# 468332_001_Power.net
KiCad netlist of a schematic drawn in Altium Designer
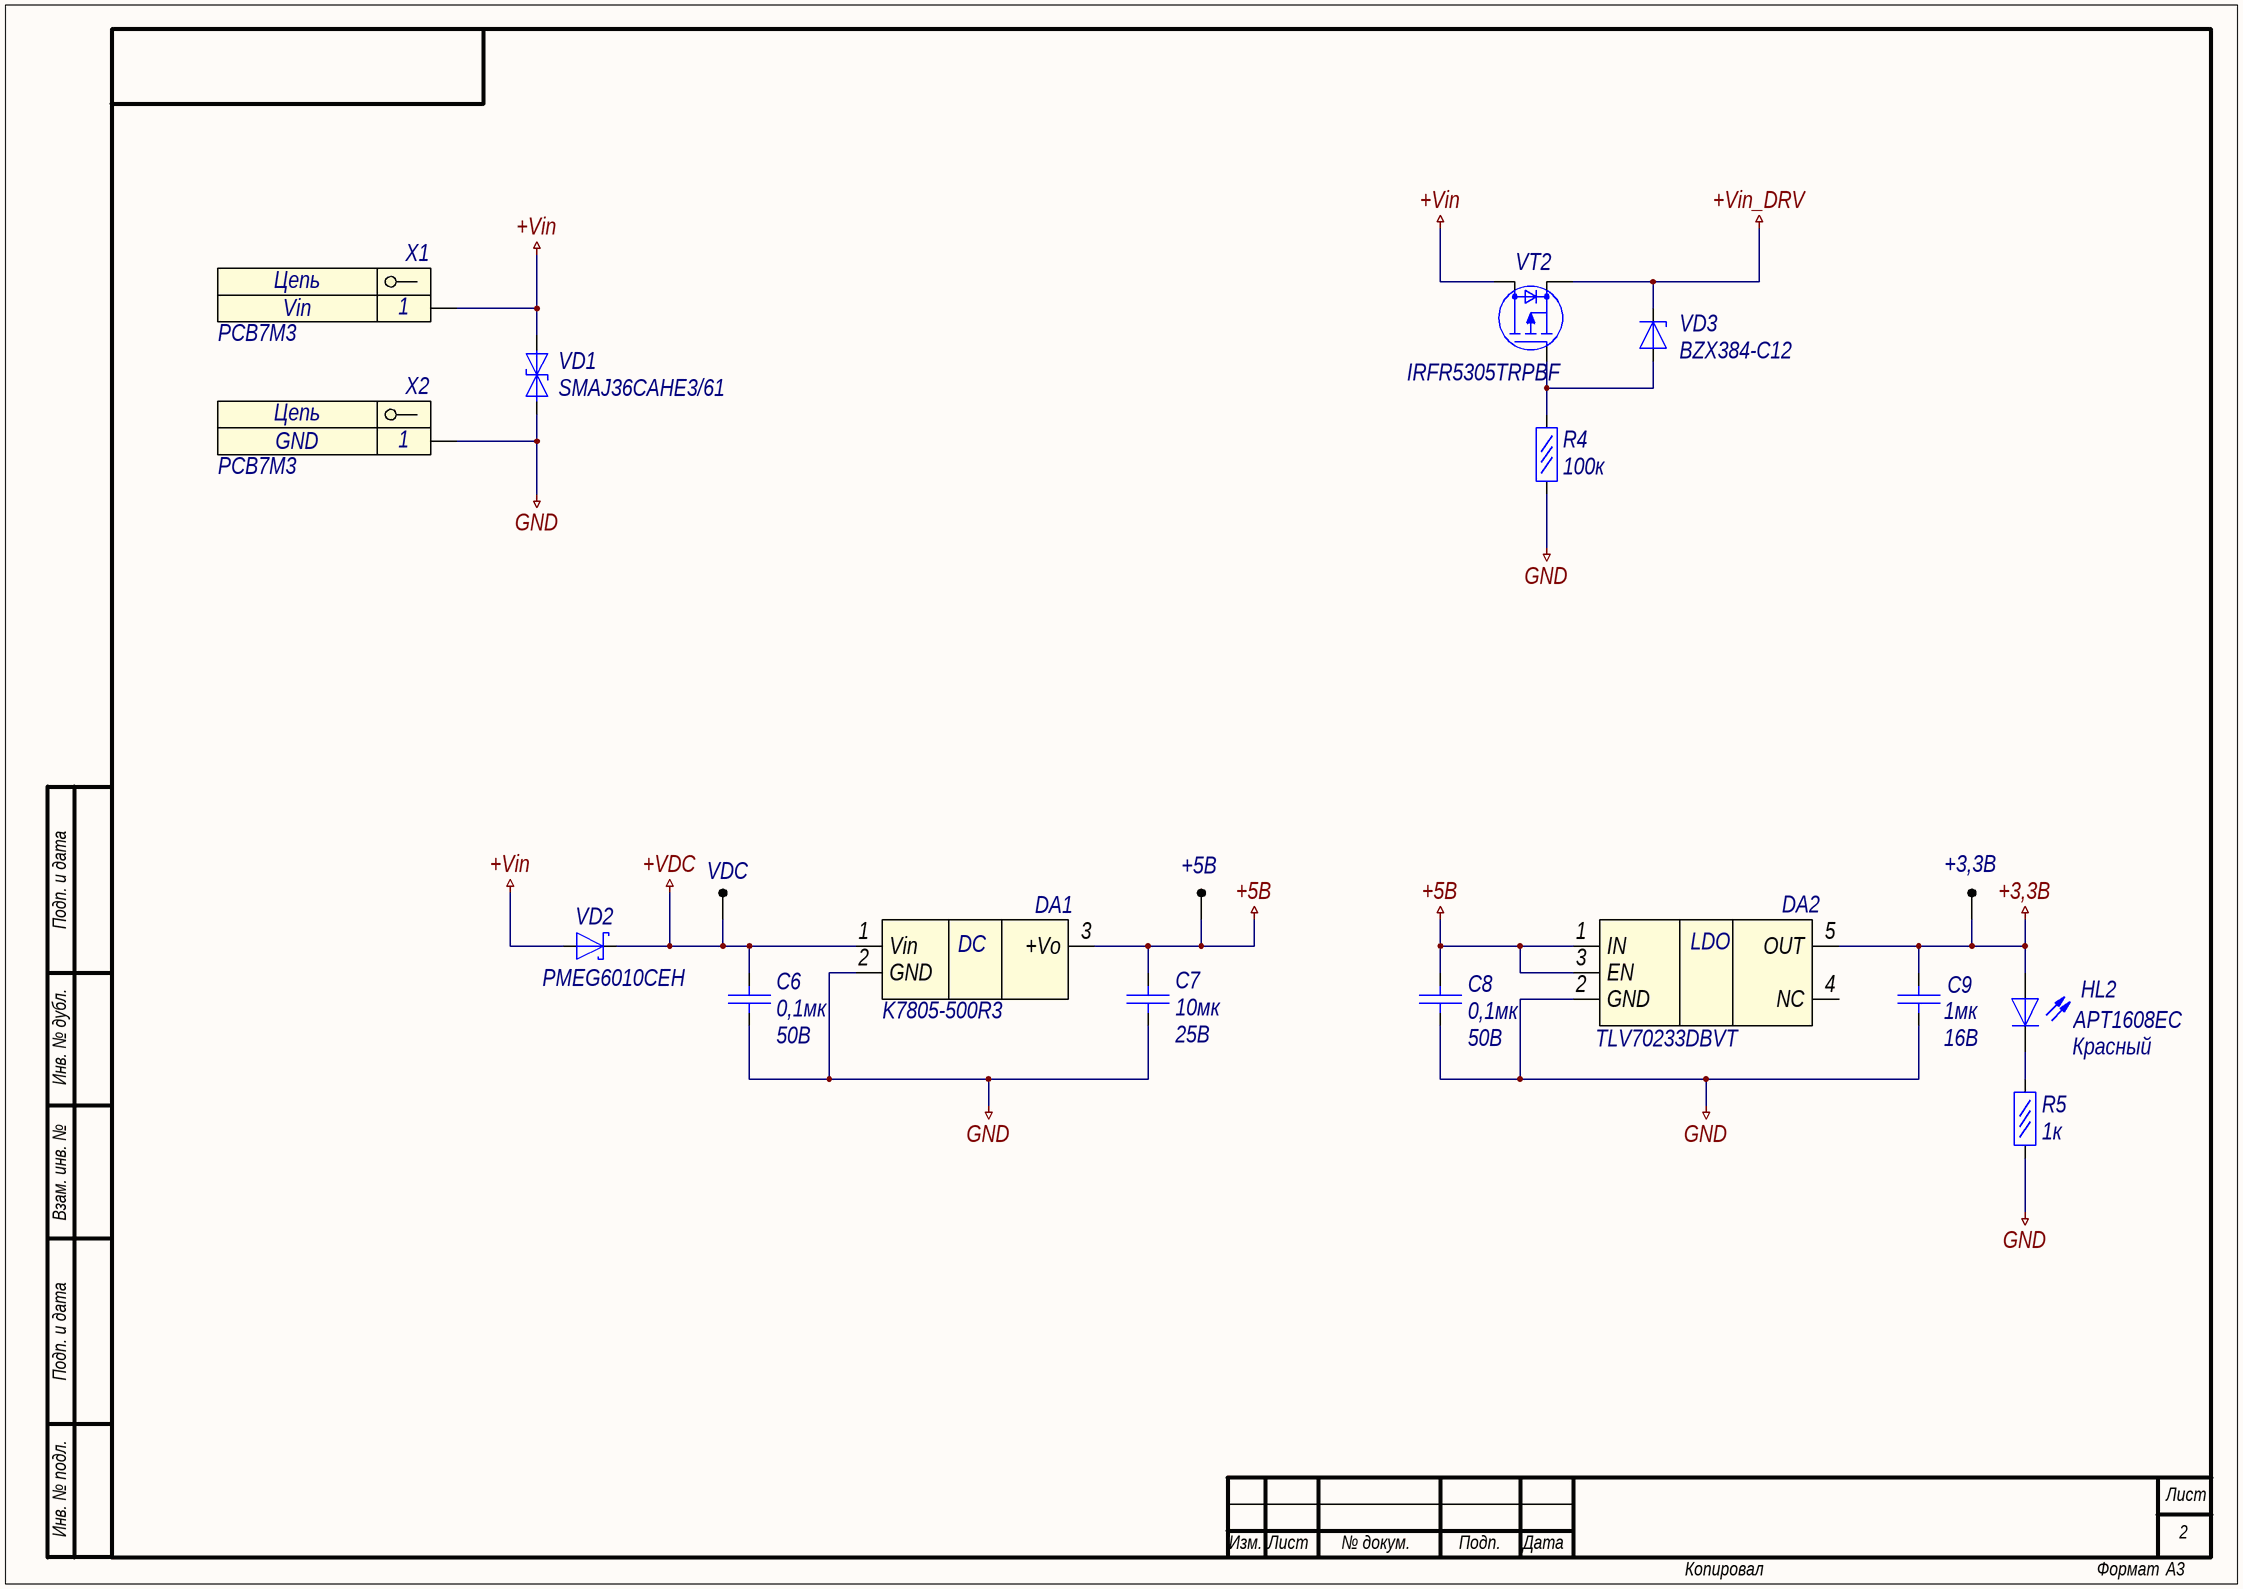
[diagram p0: РЕУН.468332.001_Power.SchDoc]

(export (version "E")
  (design (tool "Eeschema 10.0.6"))
  (components
    (comp (ref "+3,3В")
      (value "\"1\"")
      (footprint "0.5 x 1_round")
      (description "Test point")
      (libsource (lib "TarabusLib_KOR") (part "TestPoint"))
    )
    (comp (ref "+5В")
      (value "\"1\"")
      (footprint "0.5 x 1_round")
      (description "Test point")
      (libsource (lib "TarabusLib_KOR") (part "TestPoint"))
    )
    (comp (ref "C6")
      (value "0,1мк")
      (footprint "C0805_AA")
      (description "Конденсатор кер.")
      (fields (field (name "VOLTAGE") "50В"))
      (libsource (lib "Library_Diana") (part "Конденсатор кер."))
    )
    (comp (ref "C7")
      (value "10мк")
      (footprint "C0805_AA")
      (description "Конденсатор кер.")
      (fields (field (name "VOLTAGE") "25В"))
      (libsource (lib "Library_Diana") (part "Конденсатор кер."))
    )
    (comp (ref "C8")
      (value "0,1мк")
      (footprint "C0805_AA")
      (description "Конденсатор кер.")
      (fields (field (name "VOLTAGE") "50В"))
      (libsource (lib "Library_Diana") (part "Конденсатор кер."))
    )
    (comp (ref "C9")
      (value "1мк")
      (footprint "C0805_AA")
      (description "Конденсатор кер.")
      (fields (field (name "VOLTAGE") "16В"))
      (libsource (lib "Library_Diana") (part "Конденсатор кер."))
    )
    (comp (ref "DA1")
      (value "K7805-500R3")
      (description "DC/DC преобразователь неизолированный")
      (libsource (lib "Library_Diana") (part "K78xx-500R3"))
    )
    (comp (ref "DA2")
      (value "TLV70233DBVT")
      (description "LDO Regulator")
      (libsource (lib "Library_Diana") (part "TLV702"))
    )
    (comp (ref "HL2")
      (value "APT1608EC")
      (footprint "D0603_A")
      (description "Светодиод")
      (fields (field (name "VR") "Красный"))
      (libsource (lib "Library_Diana") (part "LED_R"))
    )
    (comp (ref "R4")
      (value "100к")
      (footprint "R1206")
      (description "Резистор 0,05Вт")
      (libsource (lib "Library_Diana") (part "Резистор  0,05Вт"))
    )
    (comp (ref "R5")
      (value "1к")
      (footprint "R1206")
      (description "Резистор 0,05Вт")
      (libsource (lib "Library_Diana") (part "Резистор  0,05Вт"))
    )
    (comp (ref "VD1")
      (value "SMAJ36CAHE3/61")
      (description "Ограничитель напряжения односторонний")
      (fields (field (name "NAME") "SMAJ36CAHE3/61"))
      (libsource (lib "Library_Diana") (part "diode-2tvs"))
    )
    (comp (ref "VD2")
      (value "PMEG6010CEH")
      (footprint "SOD123_A")
      (description "Диод Шоттки")
      (libsource (lib "Library_Diana") (part "DiodeSchottky"))
    )
    (comp (ref "VD3")
      (value "BZX384-C12")
      (footprint "SOT23-2_A")
      (description "Стабилитрон")
      (libsource (lib "Library_Diana") (part "DiodeZener"))
    )
    (comp (ref "VDC")
      (value "\"1\"")
      (footprint "0.5 x 1_round")
      (description "Test point")
      (libsource (lib "TarabusLib_KOR") (part "TestPoint"))
    )
    (comp (ref "VT2")
      (value "IRFR5305TRPBF")
      (footprint "SOT23-3_A")
      (description "P-MOSFET")
      (libsource (lib "Library_Diana") (part "P-MOSFET"))
    )
    (comp (ref "X1")
      (value "PCB7M3")
      (description "Разъем - 1 конт. клемма")
      (fields (field (name "NAME") "PCB7M3"))
      (libsource (lib "Library_Diana") (part "x1-k"))
    )
    (comp (ref "X2")
      (value "PCB7M3")
      (description "Разъем - 1 конт. клемма")
      (fields (field (name "NAME") "PCB7M3"))
      (libsource (lib "Library_Diana") (part "x1-k"))
    )
  )
  (nets
    (net (code "1") (name "+3,3В") (class "Default")
      (node (ref "+3,3В") (pin "1") (pinfunction "1_1") (pintype "passive"))
      (node (ref "C9") (pin "2") (pinfunction "2_2") (pintype "passive"))
      (node (ref "DA2") (pin "5") (pinfunction "OUT_5") (pintype "passive"))
      (node (ref "HL2") (pin "1") (pinfunction "Анод_1") (pintype "passive"))
    )
    (net (code "2") (name "+5В") (class "Default")
      (node (ref "+5В") (pin "1") (pinfunction "1_1") (pintype "passive"))
      (node (ref "C7") (pin "2") (pinfunction "2_2") (pintype "passive"))
      (node (ref "C8") (pin "2") (pinfunction "2_2") (pintype "passive"))
      (node (ref "DA1") (pin "3") (pinfunction "+Vo_3") (pintype "power_in"))
      (node (ref "DA2") (pin "1") (pinfunction "IN_1") (pintype "passive"))
      (node (ref "DA2") (pin "3") (pinfunction "EN_3") (pintype "passive"))
    )
    (net (code "3") (name "+VDC") (class "Default")
      (node (ref "C6") (pin "2") (pinfunction "2_2") (pintype "passive"))
      (node (ref "DA1") (pin "1") (pinfunction "Vin_1") (pintype "power_in"))
      (node (ref "VD2") (pin "1") (pinfunction "K_1") (pintype "passive"))
      (node (ref "VDC") (pin "1") (pinfunction "1_1") (pintype "passive"))
    )
    (net (code "4") (name "+Vin") (class "Default")
      (node (ref "VD1") (pin "2") (pinfunction "K_2") (pintype "passive"))
      (node (ref "VD2") (pin "2") (pinfunction "A_2") (pintype "passive"))
      (node (ref "VT2") (pin "3") (pinfunction "D_3") (pintype "passive"))
      (node (ref "X1") (pin "1") (pinfunction "1_1") (pintype "passive"))
    )
    (net (code "5") (name "+Vin_DRV") (class "Default")
      (node (ref "VD3") (pin "1") (pinfunction "K_1") (pintype "passive"))
      (node (ref "VT2") (pin "2") (pinfunction "S_2") (pintype "passive"))
    )
    (net (code "6") (name "GND") (class "Default")
      (node (ref "C6") (pin "1") (pinfunction "1_1") (pintype "passive"))
      (node (ref "C7") (pin "1") (pinfunction "1_1") (pintype "passive"))
      (node (ref "C8") (pin "1") (pinfunction "1_1") (pintype "passive"))
      (node (ref "C9") (pin "1") (pinfunction "1_1") (pintype "passive"))
      (node (ref "DA1") (pin "2") (pinfunction "GND_2") (pintype "power_in"))
      (node (ref "DA2") (pin "2") (pinfunction "GND_2") (pintype "passive"))
      (node (ref "R4") (pin "1") (pinfunction "1_1") (pintype "passive"))
      (node (ref "R5") (pin "1") (pinfunction "1_1") (pintype "passive"))
      (node (ref "VD1") (pin "1") (pinfunction "A_1") (pintype "passive"))
      (node (ref "X2") (pin "1") (pinfunction "1_1") (pintype "passive"))
    )
    (net (code "7") (name "Net-(HL2-Катод)") (class "Default")
      (node (ref "HL2") (pin "2") (pinfunction "Катод_2") (pintype "passive"))
      (node (ref "R5") (pin "2") (pinfunction "2_2") (pintype "passive"))
    )
    (net (code "8") (name "Net-(VD3-A)") (class "Default")
      (node (ref "R4") (pin "2") (pinfunction "2_2") (pintype "passive"))
      (node (ref "VD3") (pin "2") (pinfunction "A_2") (pintype "passive"))
      (node (ref "VT2") (pin "1") (pinfunction "G_1") (pintype "passive"))
    )
    (net (code "9") (name "unconnected-(DA2-NC-Pad4)") (class "Default")
      (node (ref "DA2") (pin "4") (pinfunction "NC_4") (pintype "passive"))
    )
  )
)
